# penghitopoco.net
KiCad netlist of a schematic drawn in EAGLE
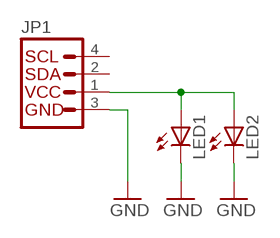
[diagram p0: schematic, sheet 1]

(export (version "E")
  (design (tool "Eeschema 10.0.6"))
  (components
    (comp (ref "JP1")
      (value "I2C_STANDARDI2C_SAO")
      (footprint "eagle-import:2X2")
      (libsource (lib "eagle-import") (part "I2C_STANDARDI2C_SAO"))
    )
    (comp (ref "LED1")
      (value "LED5MM")
      (footprint "eagle-import:LED5MM")
      (libsource (lib "eagle-import") (part "LED5MM"))
    )
    (comp (ref "LED2")
      (value "LED5MM")
      (footprint "eagle-import:LED5MM")
      (libsource (lib "eagle-import") (part "LED5MM"))
    )
  )
  (nets
    (net (code "1") (name "GND") (class "Default")
      (node (ref "JP1") (pin "3") (pinfunction "GND_3") (pintype "passive"))
      (node (ref "LED1") (pin "K") (pinfunction "C_K") (pintype "passive"))
      (node (ref "LED2") (pin "K") (pinfunction "C_K") (pintype "passive"))
    )
    (net (code "2") (name "Net-(JP1-VCC)") (class "Default")
      (node (ref "JP1") (pin "1") (pinfunction "VCC_1") (pintype "passive"))
      (node (ref "LED1") (pin "A") (pinfunction "A_A") (pintype "passive"))
      (node (ref "LED2") (pin "A") (pinfunction "A_A") (pintype "passive"))
    )
    (net (code "3") (name "unconnected-(JP1-SCL-Pad4)") (class "Default")
      (node (ref "JP1") (pin "4") (pinfunction "SCL_4") (pintype "passive"))
    )
    (net (code "4") (name "unconnected-(JP1-SDA-Pad2)") (class "Default")
      (node (ref "JP1") (pin "2") (pinfunction "SDA_2") (pintype "passive"))
    )
  )
)
